# Power.net
KiCad netlist of a schematic drawn in Altium Designer
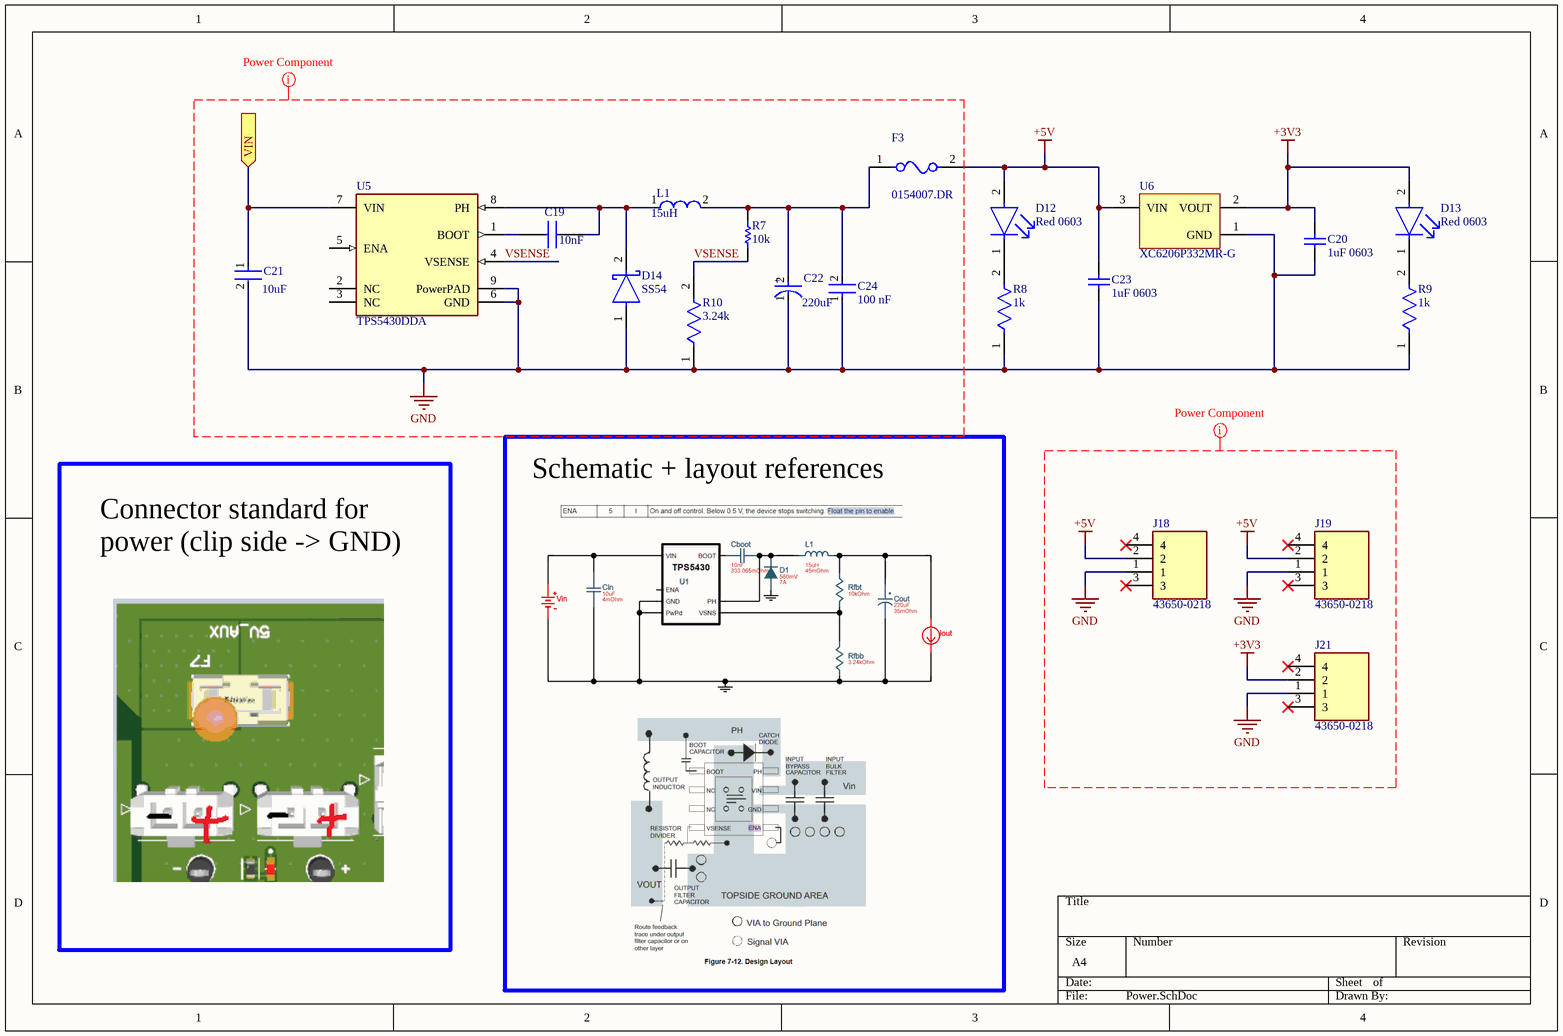
[diagram p0: Power.SchDoc]

(export (version "E")
  (design (tool "Eeschema 10.0.6"))
  (components
    (comp (ref "C19")
      (value "10nF 0603")
      (footprint "CAPC1608X95N")
      (description "50V 10nF X7R ±10% 0603 Multilayer Ceramic Capacitors MLCC - SMD/SMT ROHS")
      (fields (field (name "MANUFACTURER_PART_NUMBER") "0603B103K500NT") (field (name "CAPACITANCE") "10nF"))
      (libsource (lib "BumbleBee Autonomous Systems - NUS") (part "885382207006"))
    )
    (comp (ref "C20")
      (value "1uF 0603")
      (footprint "CAPC1608X95N")
      (libsource (lib "BumbleBee Autonomous Systems - NUS") (part "CAP"))
    )
    (comp (ref "C21")
      (value "GRM21BR61H106KE43L")
      (footprint "FP-GRM21B-0_2-e0_2_0_7-IPC_A")
      (description "Chip Multilayer Ceramic Capacitors for General Purpose, 0805, 10uF, X5R, 15%, 10%, 50V")
      (fields (field (name "TOLERANCE") "10%") (field (name "CAPACITANCE") "10uF"))
      (libsource (lib "Altium Content Vault") (part "b4654b650e69147ec39a6b967a45e02"))
    )
    (comp (ref "C22")
      (value "6TPE220MAZB")
      (footprint "FP-POSCAP-B2-MFG")
      (description "Molded Tantalum Polymer Capacitor 220uF 20% 6.3V life 1000Hours SMD 1411")
      (fields
        (field (name "VOLTAGE") "6.3V")
        (field (name "CAPACITANCE") "220uF")
        (field (name "TOLERANCE") "20%")
      )
      (libsource (lib "Altium Content Vault") (part "cf48714ba7e38822c1575c7ec0b6d1f"))
    )
    (comp (ref "C23")
      (value "1uF 0603")
      (footprint "CAPC1608X95N")
      (libsource (lib "BumbleBee Autonomous Systems - NUS") (part "CAP"))
    )
    (comp (ref "C24")
      (value "CC0603KRX7R9BB104")
      (footprint "FP-CC0603-DA-MFG")
      (description "CAP CER 0.1UF 50V X7R 0603")
      (fields
        (field (name "MANUFACTURER") "YAGEO")
        (field (name "VOLTAGE") "50 V")
        (field (name "CAPACITANCE") "100 nF")
      )
      (libsource (lib "Altium Content Vault") (part "11868f565c42a9108669ba33697ecf6"))
    )
    (comp (ref "D12")
      (value "Red 0603")
      (footprint "FP-150060RS55040-MFG")
      (description "Led Red Diffused 0603 SMD")
      (fields (field (name "MANUFACTURER PART NO.") "150060RS55040"))
      (libsource (lib "BumbleBee Autonomous Systems - NUS") (part "8706943c75ba83719d021d2fdc84c58"))
    )
    (comp (ref "D13")
      (value "Red 0603")
      (footprint "FP-150060RS55040-MFG")
      (description "Led Red Diffused 0603 SMD")
      (fields (field (name "MANUFACTURER PART NO.") "150060RS55040"))
      (libsource (lib "BumbleBee Autonomous Systems - NUS") (part "8706943c75ba83719d021d2fdc84c58"))
    )
    (comp (ref "D14")
      (value "SS54")
      (footprint "FP-403AE-MFG")
      (description "DIODE SCHOTTKY 40V 5A SMA")
      (libsource (lib "Altium Content Vault") (part "360ad2f4ac25a952324d13796385471"))
    )
    (comp (ref "F3")
      (value "0154007.DR")
      (footprint "FP-0154-MFG")
      (description "FUSE BRD MNT 7A 125VAC/VDC 2SMD")
      (fields
        (field (name "OCTOPART") "https://octopart.com/0154007.dr-littelfuse-565863")
        (field (name "MANUFACTURER") "Littelfuse Inc")
      )
      (libsource (lib "Altium Content Vault") (part "5bcf9b9f640e542cf0359d10258e979"))
    )
    (comp (ref "J18")
      (value "43650-0218")
      (footprint "SamacSys:43650-02YY_18192063")
      (description "Connector")
      (fields (field (name "MOUSER PART NUMBER") "538-43650-0218"))
      (libsource (lib "*") (part "43650-0218"))
    )
    (comp (ref "J19")
      (value "43650-0218")
      (footprint "SamacSys:43650-02YY_18192063")
      (description "Connector")
      (fields (field (name "MOUSER PART NUMBER") "538-43650-0218"))
      (libsource (lib "*") (part "43650-0218"))
    )
    (comp (ref "J21")
      (value "43650-0218")
      (footprint "SamacSys:43650-02YY_18192063")
      (description "Connector")
      (fields (field (name "MOUSER PART NUMBER") "538-43650-0218"))
      (libsource (lib "*") (part "43650-0218"))
    )
    (comp (ref "L1")
      (value "MWSA1004S-150MT")
      (footprint "FP-SPM10040-MFG")
      (description "6.5A 15uH ±20% 7A SMD,11x10mm Power Inductors ROHS")
      (fields (field (name "INDUCTANCE") "15uH"))
      (libsource (lib "Altium Content Vault") (part "725321dda6339637d4d059423bc1c3c"))
    )
    (comp (ref "R7")
      (value "0603WAF1002T5E")
      (footprint "RESC1609X50X30NL8T20")
      (description "100mW Thick Film Resistors 75V ±100ppm/℃ ±1% 10kΩ 0603 Chip Resistor - Surface Mount ROHS")
      (fields (field (name "RESISTANCE") "10k"))
      (libsource (lib "Altium Content Vault") (part "RES-2"))
    )
    (comp (ref "R8")
      (value "1k")
      (footprint "FP-RC0603-0_55-IPC_C")
      (description "RC0603FR-071KL. RES 1K OHM 1% 1/10W 0603")
      (fields (field (name "TOLERANCE") "1%"))
      (libsource (lib "Altium Content Vault") (part "1029c3af85768c4190bb7ad29bc67b5"))
    )
    (comp (ref "R9")
      (value "1k")
      (footprint "FP-RC0603-0_55-IPC_C")
      (description "RC0603FR-071KL. RES 1K OHM 1% 1/10W 0603")
      (fields (field (name "TOLERANCE") "1%"))
      (libsource (lib "Altium Content Vault") (part "1029c3af85768c4190bb7ad29bc67b5"))
    )
    (comp (ref "R10")
      (value "0603WAF3241T5E")
      (footprint "FP-CRCW0603-e3-IPC_A")
      (description "100mW Thick Film Resistors 75V ±100ppm/℃ ±1% 3.24kΩ 0603 Chip Resistor - Surface Mount ROHS")
      (fields (field (name "RESISTANCE") "3.24k"))
      (libsource (lib "Altium Content Vault") (part "1029c3af85768c4190bb7ad29bc67b5"))
    )
    (comp (ref "U5")
      (value "TPS5430DDA")
      (footprint "FP-DDA0008J-MFG")
      (description "IC REG BUCK ADJUSTABLE 3A 8SOPWR")
      (fields
        (field (name "MANUFACTURER") "Texas Instruments")
        (field (name "OCTOPART") "https://octopart.com/tps5430dda-texas+instruments-589977")
      )
      (libsource (lib "Altium Content Vault") (part "98da629940cea6febc5630bb55159f3"))
    )
    (comp (ref "U6")
      (value "XC6206P332MR-G")
      (footprint "SOT-23-TT3_N")
      (description "200mA Fixed 3.3V Positive electrode 6V SOT-23-3L Linear Voltage Regulators (LDO) ROHS")
      (libsource (lib "Altium Content Vault") (part "PM-LINEREG-MCP1700-IL3"))
    )
  )
  (nets
    (net (code "1") (name "+3V3") (class "Default")
      (node (ref "C20") (pin "2") (pinfunction "2_2") (pintype "passive"))
      (node (ref "D13") (pin "2") (pinfunction "A_2") (pintype "passive"))
      (node (ref "J21") (pin "2") (pinfunction "2_2") (pintype "passive"))
      (node (ref "U6") (pin "2") (pinfunction "VOUT_2") (pintype "power_in"))
    )
    (net (code "2") (name "+5V") (class "Default")
      (node (ref "C23") (pin "2") (pinfunction "2_2") (pintype "passive"))
      (node (ref "D12") (pin "2") (pinfunction "A_2") (pintype "passive"))
      (node (ref "F3") (pin "2") (pinfunction "2_2") (pintype "passive"))
      (node (ref "J18") (pin "2") (pinfunction "2_2") (pintype "passive"))
      (node (ref "J19") (pin "2") (pinfunction "2_2") (pintype "passive"))
      (node (ref "U6") (pin "3") (pinfunction "VIN_3") (pintype "power_in"))
    )
    (net (code "3") (name "/VIN") (class "Default")
      (node (ref "C21") (pin "1") (pinfunction "1_1") (pintype "passive"))
      (node (ref "U5") (pin "7") (pinfunction "VIN_7") (pintype "power_in"))
    )
    (net (code "4") (name "/VSENSE") (class "Default")
      (node (ref "R10") (pin "2") (pinfunction "2_2") (pintype "passive"))
      (node (ref "R7") (pin "1") (pinfunction "1_1") (pintype "passive"))
      (node (ref "U5") (pin "4") (pinfunction "VSENSE_4") (pintype "input"))
    )
    (net (code "5") (name "GND") (class "Default")
      (node (ref "C20") (pin "1") (pinfunction "1_1") (pintype "passive"))
      (node (ref "C21") (pin "2") (pinfunction "2_2") (pintype "passive"))
      (node (ref "C22") (pin "1") (pinfunction "C_1") (pintype "passive"))
      (node (ref "C23") (pin "1") (pinfunction "1_1") (pintype "passive"))
      (node (ref "C24") (pin "1") (pinfunction "1_1") (pintype "passive"))
      (node (ref "D14") (pin "1") (pinfunction "A_1") (pintype "passive"))
      (node (ref "J18") (pin "1") (pinfunction "1_1") (pintype "passive"))
      (node (ref "J19") (pin "1") (pinfunction "1_1") (pintype "passive"))
      (node (ref "J21") (pin "1") (pinfunction "1_1") (pintype "passive"))
      (node (ref "R10") (pin "1") (pinfunction "1_1") (pintype "passive"))
      (node (ref "R8") (pin "1") (pinfunction "1_1") (pintype "passive"))
      (node (ref "R9") (pin "1") (pinfunction "1_1") (pintype "passive"))
      (node (ref "U5") (pin "6") (pinfunction "GND_6") (pintype "power_in"))
      (node (ref "U5") (pin "9") (pinfunction "PowerPAD_9") (pintype "power_in"))
      (node (ref "U6") (pin "1") (pinfunction "GND_1") (pintype "power_in"))
    )
    (net (code "6") (name "Net-(C22-A)") (class "Default")
      (node (ref "C22") (pin "2") (pinfunction "A_2") (pintype "passive"))
      (node (ref "C24") (pin "2") (pinfunction "2_2") (pintype "passive"))
      (node (ref "F3") (pin "1") (pinfunction "1_1") (pintype "passive"))
      (node (ref "L1") (pin "2") (pinfunction "2_2") (pintype "passive"))
      (node (ref "R7") (pin "2") (pinfunction "2_2") (pintype "passive"))
    )
    (net (code "7") (name "Net-(D12-C)") (class "Default")
      (node (ref "D12") (pin "1") (pinfunction "C_1") (pintype "passive"))
      (node (ref "R8") (pin "2") (pinfunction "2_2") (pintype "passive"))
    )
    (net (code "8") (name "Net-(D13-C)") (class "Default")
      (node (ref "D13") (pin "1") (pinfunction "C_1") (pintype "passive"))
      (node (ref "R9") (pin "2") (pinfunction "2_2") (pintype "passive"))
    )
    (net (code "9") (name "Net-(D14-C)") (class "Default")
      (node (ref "C19") (pin "2") (pinfunction "2_2") (pintype "passive"))
      (node (ref "D14") (pin "2") (pinfunction "C_2") (pintype "passive"))
      (node (ref "L1") (pin "1") (pinfunction "1_1") (pintype "passive"))
      (node (ref "U5") (pin "8") (pinfunction "PH_8") (pintype "input"))
    )
    (net (code "10") (name "Net-(U5-BOOT)") (class "Default")
      (node (ref "C19") (pin "1") (pinfunction "1_1") (pintype "passive"))
      (node (ref "U5") (pin "1") (pinfunction "BOOT_1") (pintype "output"))
    )
    (net (code "11") (name "unconnected-(J18-Pad3)") (class "Default")
      (node (ref "J18") (pin "3") (pinfunction "3_3") (pintype "passive+no_connect"))
    )
    (net (code "12") (name "unconnected-(J18-Pad4)") (class "Default")
      (node (ref "J18") (pin "4") (pinfunction "4_4") (pintype "passive+no_connect"))
    )
    (net (code "13") (name "unconnected-(J19-Pad3)") (class "Default")
      (node (ref "J19") (pin "3") (pinfunction "3_3") (pintype "passive+no_connect"))
    )
    (net (code "14") (name "unconnected-(J19-Pad4)") (class "Default")
      (node (ref "J19") (pin "4") (pinfunction "4_4") (pintype "passive+no_connect"))
    )
    (net (code "15") (name "unconnected-(J21-Pad3)") (class "Default")
      (node (ref "J21") (pin "3") (pinfunction "3_3") (pintype "passive+no_connect"))
    )
    (net (code "16") (name "unconnected-(J21-Pad4)") (class "Default")
      (node (ref "J21") (pin "4") (pinfunction "4_4") (pintype "passive+no_connect"))
    )
    (net (code "17") (name "unconnected-(U5-ENA-Pad5)") (class "Default")
      (node (ref "U5") (pin "5") (pinfunction "ENA_5") (pintype "input"))
    )
    (net (code "18") (name "unconnected-(U5-NC-Pad2)") (class "Default")
      (node (ref "U5") (pin "2") (pinfunction "NC_2") (pintype "passive"))
    )
    (net (code "19") (name "unconnected-(U5-NC-Pad3)") (class "Default")
      (node (ref "U5") (pin "3") (pinfunction "NC_3") (pintype "passive"))
    )
  )
)
